# HMI_Board.net
KiCad netlist of a schematic drawn in EAGLE
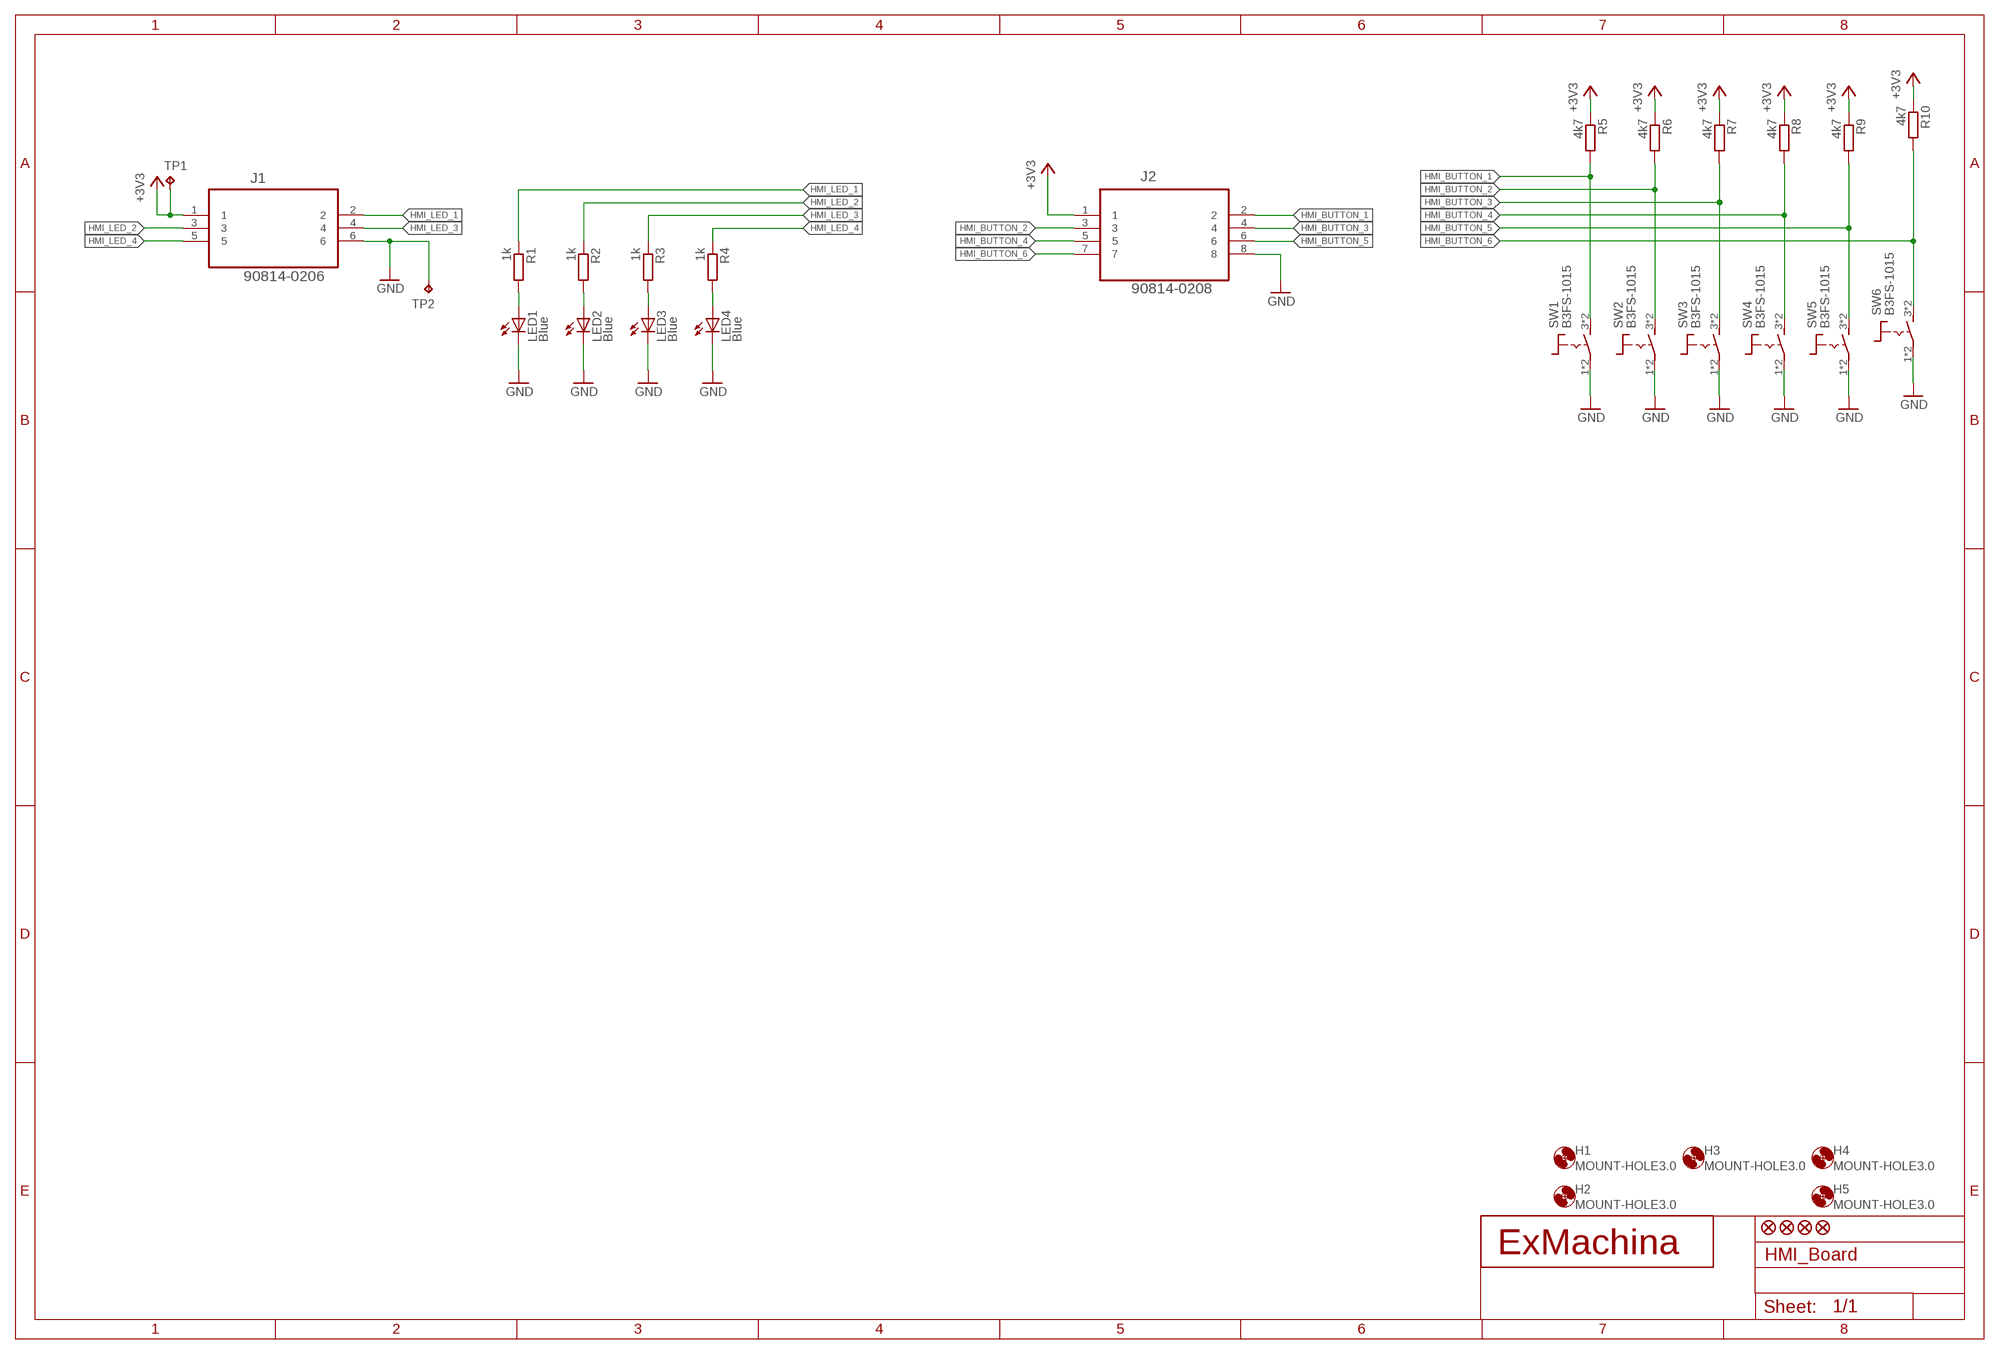
[diagram p0: schematic, sheet 1]

(export (version "E")
  (design (tool "Eeschema 10.0.6"))
  (components
    (comp (ref "H1")
      (value "MOUNT-HOLE3.0")
      (footprint "eagle-import:3,0")
      (libsource (lib "eagle-import") (part "MOUNT-HOLE3.0"))
    )
    (comp (ref "H2")
      (value "MOUNT-HOLE3.0")
      (footprint "eagle-import:3,0")
      (libsource (lib "eagle-import") (part "MOUNT-HOLE3.0"))
    )
    (comp (ref "H3")
      (value "MOUNT-HOLE3.0")
      (footprint "eagle-import:3,0")
      (libsource (lib "eagle-import") (part "MOUNT-HOLE3.0"))
    )
    (comp (ref "H4")
      (value "MOUNT-HOLE3.0")
      (footprint "eagle-import:3,0")
      (libsource (lib "eagle-import") (part "MOUNT-HOLE3.0"))
    )
    (comp (ref "H5")
      (value "MOUNT-HOLE3.0")
      (footprint "eagle-import:3,0")
      (libsource (lib "eagle-import") (part "MOUNT-HOLE3.0"))
    )
    (comp (ref "J1")
      (value "90814-0206")
      (footprint "eagle-import:MOLEX_90814-0206")
      (libsource (lib "eagle-import") (part "90814-0206"))
    )
    (comp (ref "J2")
      (value "90814-0208")
      (footprint "eagle-import:MOLEX_90814-0208")
      (libsource (lib "eagle-import") (part "90814-0208"))
    )
    (comp (ref "JP1")
      (value "FIDUCIAL1X2")
      (footprint "eagle-import:FIDUCIAL-1X2")
      (libsource (lib "eagle-import") (part "FIDUCIAL1X2"))
    )
    (comp (ref "JP2")
      (value "FIDUCIAL1X2")
      (footprint "eagle-import:FIDUCIAL-1X2")
      (libsource (lib "eagle-import") (part "FIDUCIAL1X2"))
    )
    (comp (ref "JP3")
      (value "FIDUCIAL1X2")
      (footprint "eagle-import:FIDUCIAL-1X2")
      (libsource (lib "eagle-import") (part "FIDUCIAL1X2"))
    )
    (comp (ref "JP4")
      (value "FIDUCIAL1X2")
      (footprint "eagle-import:FIDUCIAL-1X2")
      (libsource (lib "eagle-import") (part "FIDUCIAL1X2"))
    )
    (comp (ref "LED1")
      (value "Blue")
      (footprint "eagle-import:SML0603")
      (libsource (lib "eagle-import") (part "LEDSML0603"))
    )
    (comp (ref "LED2")
      (value "Blue")
      (footprint "eagle-import:SML0603")
      (libsource (lib "eagle-import") (part "LEDSML0603"))
    )
    (comp (ref "LED3")
      (value "Blue")
      (footprint "eagle-import:SML0603")
      (libsource (lib "eagle-import") (part "LEDSML0603"))
    )
    (comp (ref "LED4")
      (value "Blue")
      (footprint "eagle-import:SML0603")
      (libsource (lib "eagle-import") (part "LEDSML0603"))
    )
    (comp (ref "R1")
      (value "1k")
      (footprint "eagle-import:R0603")
      (libsource (lib "eagle-import") (part "R-EU_R0603"))
    )
    (comp (ref "R2")
      (value "1k")
      (footprint "eagle-import:R0603")
      (libsource (lib "eagle-import") (part "R-EU_R0603"))
    )
    (comp (ref "R3")
      (value "1k")
      (footprint "eagle-import:R0603")
      (libsource (lib "eagle-import") (part "R-EU_R0603"))
    )
    (comp (ref "R4")
      (value "1k")
      (footprint "eagle-import:R0603")
      (libsource (lib "eagle-import") (part "R-EU_R0603"))
    )
    (comp (ref "R5")
      (value "4k7")
      (footprint "eagle-import:R0603")
      (libsource (lib "eagle-import") (part "R-EU_R0603"))
    )
    (comp (ref "R6")
      (value "4k7")
      (footprint "eagle-import:R0603")
      (libsource (lib "eagle-import") (part "R-EU_R0603"))
    )
    (comp (ref "R7")
      (value "4k7")
      (footprint "eagle-import:R0603")
      (libsource (lib "eagle-import") (part "R-EU_R0603"))
    )
    (comp (ref "R8")
      (value "4k7")
      (footprint "eagle-import:R0603")
      (libsource (lib "eagle-import") (part "R-EU_R0603"))
    )
    (comp (ref "R9")
      (value "4k7")
      (footprint "eagle-import:R0603")
      (libsource (lib "eagle-import") (part "R-EU_R0603"))
    )
    (comp (ref "R10")
      (value "4k7")
      (footprint "eagle-import:R0603")
      (libsource (lib "eagle-import") (part "R-EU_R0603"))
    )
    (comp (ref "SW1")
      (value "B3FS-1015")
      (footprint "eagle-import:B3FS")
      (libsource (lib "eagle-import") (part "B3FS-1015"))
    )
    (comp (ref "SW2")
      (value "B3FS-1015")
      (footprint "eagle-import:B3FS")
      (libsource (lib "eagle-import") (part "B3FS-1015"))
    )
    (comp (ref "SW3")
      (value "B3FS-1015")
      (footprint "eagle-import:B3FS")
      (libsource (lib "eagle-import") (part "B3FS-1015"))
    )
    (comp (ref "SW4")
      (value "B3FS-1015")
      (footprint "eagle-import:B3FS")
      (libsource (lib "eagle-import") (part "B3FS-1015"))
    )
    (comp (ref "SW5")
      (value "B3FS-1015")
      (footprint "eagle-import:B3FS")
      (libsource (lib "eagle-import") (part "B3FS-1015"))
    )
    (comp (ref "SW6")
      (value "B3FS-1015")
      (footprint "eagle-import:B3FS")
      (libsource (lib "eagle-import") (part "B3FS-1015"))
    )
    (comp (ref "T1")
      (value "EXMACHINA-LOGO-NAME")
      (footprint "eagle-import:EXM-LOGO-BASELINE")
      (libsource (lib "eagle-import") (part "EXMACHINA-LOGO-NAME"))
    )
    (comp (ref "TP1")
      (value "TPB2,54")
      (footprint "eagle-import:B2,54")
      (libsource (lib "eagle-import") (part "TPB2,54"))
    )
    (comp (ref "TP2")
      (value "TPB2,54")
      (footprint "eagle-import:B2,54")
      (libsource (lib "eagle-import") (part "TPB2,54"))
    )
  )
  (nets
    (net (code "1") (name "+3V3") (class "Default")
      (node (ref "J1") (pin "1") (pinfunction "1_1") (pintype "passive"))
      (node (ref "J2") (pin "1") (pinfunction "1_1") (pintype "passive"))
      (node (ref "R10") (pin "1") (pinfunction "1_1") (pintype "passive"))
      (node (ref "R5") (pin "1") (pinfunction "1_1") (pintype "passive"))
      (node (ref "R6") (pin "1") (pinfunction "1_1") (pintype "passive"))
      (node (ref "R7") (pin "1") (pinfunction "1_1") (pintype "passive"))
      (node (ref "R8") (pin "1") (pinfunction "1_1") (pintype "passive"))
      (node (ref "R9") (pin "1") (pinfunction "1_1") (pintype "passive"))
      (node (ref "TP1") (pin "TP") (pinfunction "TP_TP") (pintype "input"))
    )
    (net (code "2") (name "GND") (class "Default")
      (node (ref "J1") (pin "6") (pinfunction "6_6") (pintype "passive"))
      (node (ref "J2") (pin "8") (pinfunction "8_8") (pintype "passive"))
      (node (ref "LED1") (pin "C") (pinfunction "C_C") (pintype "passive"))
      (node (ref "LED2") (pin "C") (pinfunction "C_C") (pintype "passive"))
      (node (ref "LED3") (pin "C") (pinfunction "C_C") (pintype "passive"))
      (node (ref "LED4") (pin "C") (pinfunction "C_C") (pintype "passive"))
      (node (ref "SW1") (pin "1") (pinfunction "2_1") (pintype "passive"))
      (node (ref "SW1") (pin "2") (pinfunction "2_2") (pintype "passive"))
      (node (ref "SW2") (pin "1") (pinfunction "2_1") (pintype "passive"))
      (node (ref "SW2") (pin "2") (pinfunction "2_2") (pintype "passive"))
      (node (ref "SW3") (pin "1") (pinfunction "2_1") (pintype "passive"))
      (node (ref "SW3") (pin "2") (pinfunction "2_2") (pintype "passive"))
      (node (ref "SW4") (pin "1") (pinfunction "2_1") (pintype "passive"))
      (node (ref "SW4") (pin "2") (pinfunction "2_2") (pintype "passive"))
      (node (ref "SW5") (pin "1") (pinfunction "2_1") (pintype "passive"))
      (node (ref "SW5") (pin "2") (pinfunction "2_2") (pintype "passive"))
      (node (ref "SW6") (pin "1") (pinfunction "2_1") (pintype "passive"))
      (node (ref "SW6") (pin "2") (pinfunction "2_2") (pintype "passive"))
      (node (ref "TP2") (pin "TP") (pinfunction "TP_TP") (pintype "input"))
    )
    (net (code "3") (name "HMI_BUTTON_1") (class "Default")
      (node (ref "J2") (pin "2") (pinfunction "2_2") (pintype "passive"))
      (node (ref "R5") (pin "2") (pinfunction "2_2") (pintype "passive"))
      (node (ref "SW1") (pin "3") (pinfunction "1_3") (pintype "passive"))
      (node (ref "SW1") (pin "4") (pinfunction "1_4") (pintype "passive"))
    )
    (net (code "4") (name "HMI_BUTTON_2") (class "Default")
      (node (ref "J2") (pin "3") (pinfunction "3_3") (pintype "passive"))
      (node (ref "R6") (pin "2") (pinfunction "2_2") (pintype "passive"))
      (node (ref "SW2") (pin "3") (pinfunction "1_3") (pintype "passive"))
      (node (ref "SW2") (pin "4") (pinfunction "1_4") (pintype "passive"))
    )
    (net (code "5") (name "HMI_BUTTON_3") (class "Default")
      (node (ref "J2") (pin "4") (pinfunction "4_4") (pintype "passive"))
      (node (ref "R7") (pin "2") (pinfunction "2_2") (pintype "passive"))
      (node (ref "SW3") (pin "3") (pinfunction "1_3") (pintype "passive"))
      (node (ref "SW3") (pin "4") (pinfunction "1_4") (pintype "passive"))
    )
    (net (code "6") (name "HMI_BUTTON_4") (class "Default")
      (node (ref "J2") (pin "5") (pinfunction "5_5") (pintype "passive"))
      (node (ref "R8") (pin "2") (pinfunction "2_2") (pintype "passive"))
      (node (ref "SW4") (pin "3") (pinfunction "1_3") (pintype "passive"))
      (node (ref "SW4") (pin "4") (pinfunction "1_4") (pintype "passive"))
    )
    (net (code "7") (name "HMI_BUTTON_5") (class "Default")
      (node (ref "J2") (pin "6") (pinfunction "6_6") (pintype "passive"))
      (node (ref "R9") (pin "2") (pinfunction "2_2") (pintype "passive"))
      (node (ref "SW5") (pin "3") (pinfunction "1_3") (pintype "passive"))
      (node (ref "SW5") (pin "4") (pinfunction "1_4") (pintype "passive"))
    )
    (net (code "8") (name "HMI_BUTTON_6") (class "Default")
      (node (ref "J2") (pin "7") (pinfunction "7_7") (pintype "passive"))
      (node (ref "R10") (pin "2") (pinfunction "2_2") (pintype "passive"))
      (node (ref "SW6") (pin "3") (pinfunction "1_3") (pintype "passive"))
      (node (ref "SW6") (pin "4") (pinfunction "1_4") (pintype "passive"))
    )
    (net (code "9") (name "HMI_LED_1") (class "Default")
      (node (ref "J1") (pin "2") (pinfunction "2_2") (pintype "passive"))
      (node (ref "R1") (pin "1") (pinfunction "1_1") (pintype "passive"))
    )
    (net (code "10") (name "HMI_LED_2") (class "Default")
      (node (ref "J1") (pin "3") (pinfunction "3_3") (pintype "passive"))
      (node (ref "R2") (pin "1") (pinfunction "1_1") (pintype "passive"))
    )
    (net (code "11") (name "HMI_LED_3") (class "Default")
      (node (ref "J1") (pin "4") (pinfunction "4_4") (pintype "passive"))
      (node (ref "R3") (pin "1") (pinfunction "1_1") (pintype "passive"))
    )
    (net (code "12") (name "HMI_LED_4") (class "Default")
      (node (ref "J1") (pin "5") (pinfunction "5_5") (pintype "passive"))
      (node (ref "R4") (pin "1") (pinfunction "1_1") (pintype "passive"))
    )
    (net (code "13") (name "Net-(LED1-PadA)") (class "Default")
      (node (ref "LED1") (pin "A") (pinfunction "A_A") (pintype "passive"))
      (node (ref "R1") (pin "2") (pinfunction "2_2") (pintype "passive"))
    )
    (net (code "14") (name "Net-(LED2-PadA)") (class "Default")
      (node (ref "LED2") (pin "A") (pinfunction "A_A") (pintype "passive"))
      (node (ref "R2") (pin "2") (pinfunction "2_2") (pintype "passive"))
    )
    (net (code "15") (name "Net-(LED3-PadA)") (class "Default")
      (node (ref "LED3") (pin "A") (pinfunction "A_A") (pintype "passive"))
      (node (ref "R3") (pin "2") (pinfunction "2_2") (pintype "passive"))
    )
    (net (code "16") (name "Net-(LED4-PadA)") (class "Default")
      (node (ref "LED4") (pin "A") (pinfunction "A_A") (pintype "passive"))
      (node (ref "R4") (pin "2") (pinfunction "2_2") (pintype "passive"))
    )
  )
)
